# LVL_Shift.net
KiCad netlist of a schematic drawn in Altium Designer
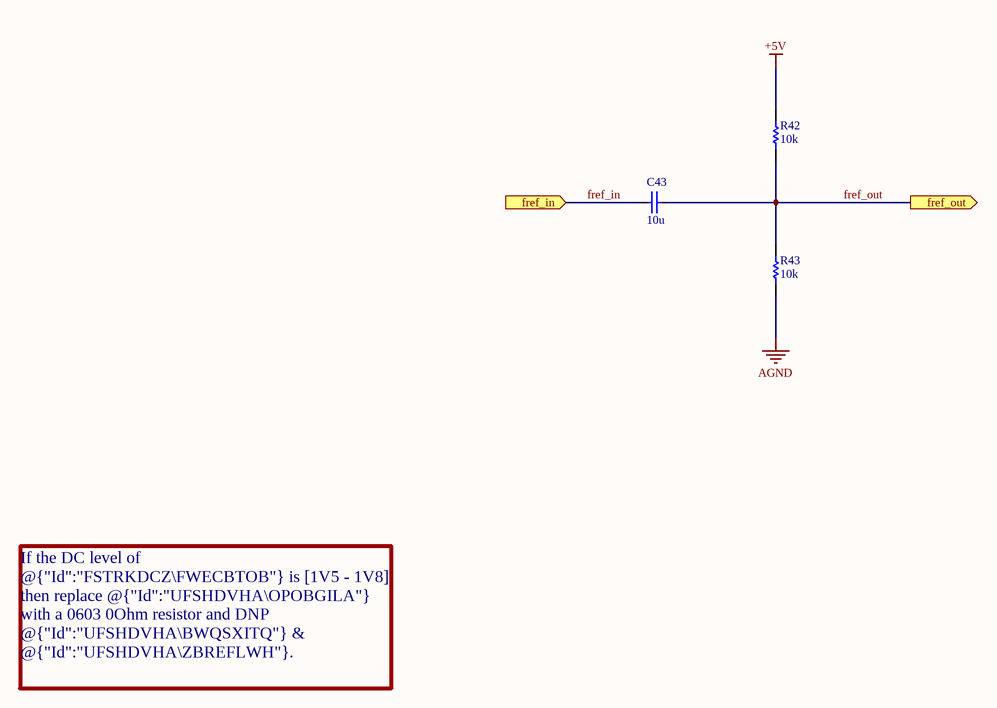
[diagram p0: LVL_Shift.SchDoc]

(export (version "E")
  (design (tool "Eeschema 10.0.6"))
  (components
    (comp (ref "C43") (value "10u") (footprint "CAP_0603") (libsource (lib "IIS-Lib_TW") (part "Cap")))
    (comp (ref "R42") (value "10k") (footprint "RES_0603") (libsource (lib "IIS-Lib_TW") (part "Res")))
    (comp (ref "R43") (value "10k") (footprint "RES_0603") (libsource (lib "IIS-Lib_TW") (part "Res")))
  )
  (nets
    (net (code "1") (name "+5V") (class "Default")
      (node (ref "R42") (pin "2") (pinfunction "2_2") (pintype "passive"))
    )
    (net (code "2") (name "/fref_in") (class "Default")
      (node (ref "C43") (pin "2") (pinfunction "2_2") (pintype "passive"))
    )
    (net (code "3") (name "/fref_out") (class "Default")
      (node (ref "C43") (pin "1") (pinfunction "1_1") (pintype "passive"))
      (node (ref "R42") (pin "1") (pinfunction "1_1") (pintype "passive"))
      (node (ref "R43") (pin "2") (pinfunction "2_2") (pintype "passive"))
    )
    (net (code "4") (name "AGND") (class "Default")
      (node (ref "R43") (pin "1") (pinfunction "1_1") (pintype "passive"))
    )
  )
)
